# motor_controller.net
KiCad netlist of a schematic drawn in Altium Designer
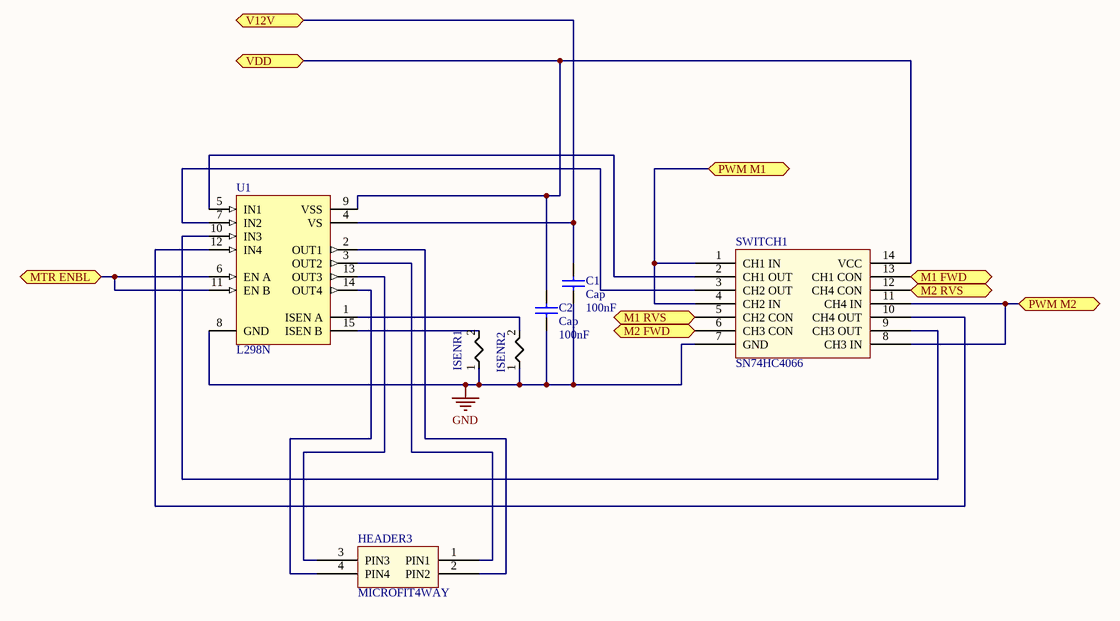
[diagram p0: motor_controller.SchDoc]

(export (version "E")
  (design (tool "Eeschema 10.0.6"))
  (components
    (comp (ref "C1")
      (value "Cap")
      (footprint "RAD-0.3")
      (description "Capacitor")
      (fields (field (name "ALTIUM_VALUE") "100nF") (field (name "PUBLISHER") "Altium Limited"))
      (libsource (lib "Miscellaneous Devices") (part "Cap"))
    )
    (comp (ref "C2")
      (value "Cap")
      (footprint "RAD-0.3")
      (description "Capacitor")
      (fields (field (name "ALTIUM_VALUE") "100nF") (field (name "PUBLISHER") "Altium Limited"))
      (libsource (lib "Miscellaneous Devices") (part "Cap"))
    )
    (comp (ref "HEADER3")
      (value "MICROFIT4WAY")
      (footprint "MULTIFIT-4WAY")
      (description "MICROFIT4WAY HEADER")
      (libsource (lib "MICROFIT_4WAY") (part "MICROFIT4WAY HEADER"))
    )
    (comp (ref "ISENR1")
      (value "CURRENT SENSE RESISTOR")
      (footprint "CURRENT_SENSE_RESISTOR")
      (libsource (lib "CURRENT_SENSE_R") (part "CURRENT SENSE RESISTOR"))
    )
    (comp (ref "ISENR2")
      (value "CURRENT SENSE RESISTOR")
      (footprint "CURRENT_SENSE_RESISTOR")
      (libsource (lib "CURRENT_SENSE_R") (part "CURRENT SENSE RESISTOR"))
    )
    (comp (ref "SWITCH1")
      (value "SN74HC4066")
      (footprint "SN74HC4066_DIP")
      (description "SN74HC4066 SWITCH")
      (libsource (lib "SN74HC4066") (part "SN74HC4066 SWITCH"))
    )
    (comp (ref "U1")
      (value "L298N")
      (footprint "Multiwatt15V")
      (description "Dual Full Bridge Driver")
      (fields (field (name "PUBLISHER") "Altium Limited"))
      (libsource (lib "ST Interface DC Motor Controller") (part "L298N"))
    )
  )
  (nets
    (net (code "1") (name "/M1 FWD") (class "Default")
      (node (ref "SWITCH1") (pin "13") (pinfunction "CH1_CON_13") (pintype "passive"))
    )
    (net (code "2") (name "/M1 RVS") (class "Default")
      (node (ref "SWITCH1") (pin "5") (pinfunction "CH2_CON_5") (pintype "passive"))
    )
    (net (code "3") (name "/M2 FWD") (class "Default")
      (node (ref "SWITCH1") (pin "6") (pinfunction "CH3_CON_6") (pintype "passive"))
    )
    (net (code "4") (name "/M2 RVS") (class "Default")
      (node (ref "SWITCH1") (pin "12") (pinfunction "CH4_CON_12") (pintype "passive"))
    )
    (net (code "5") (name "/MTR ENBL") (class "Default")
      (node (ref "U1") (pin "11") (pinfunction "EN_B_11") (pintype "input"))
      (node (ref "U1") (pin "6") (pinfunction "EN_A_6") (pintype "input"))
    )
    (net (code "6") (name "/PWM M1") (class "Default")
      (node (ref "SWITCH1") (pin "1") (pinfunction "CH1_IN_1") (pintype "passive"))
      (node (ref "SWITCH1") (pin "4") (pinfunction "CH2_IN_4") (pintype "passive"))
    )
    (net (code "7") (name "/PWM M2") (class "Default")
      (node (ref "SWITCH1") (pin "11") (pinfunction "CH4_IN_11") (pintype "passive"))
      (node (ref "SWITCH1") (pin "8") (pinfunction "CH3_IN_8") (pintype "passive"))
    )
    (net (code "8") (name "/V12V") (class "Default")
      (node (ref "C1") (pin "2") (pinfunction "2_2") (pintype "passive"))
      (node (ref "U1") (pin "4") (pinfunction "VS_4") (pintype "power_in"))
    )
    (net (code "9") (name "/VDD") (class "Default")
      (node (ref "C2") (pin "2") (pinfunction "2_2") (pintype "passive"))
      (node (ref "SWITCH1") (pin "14") (pinfunction "VCC_14") (pintype "passive"))
      (node (ref "U1") (pin "9") (pinfunction "VSS_9") (pintype "power_in"))
    )
    (net (code "10") (name "GND") (class "Default")
      (node (ref "C1") (pin "1") (pinfunction "1_1") (pintype "passive"))
      (node (ref "C2") (pin "1") (pinfunction "1_1") (pintype "passive"))
      (node (ref "ISENR1") (pin "1") (pinfunction "PIN1_1") (pintype "passive"))
      (node (ref "ISENR2") (pin "1") (pinfunction "PIN1_1") (pintype "passive"))
      (node (ref "SWITCH1") (pin "7") (pinfunction "GND_7") (pintype "passive"))
      (node (ref "U1") (pin "8") (pinfunction "GND_8") (pintype "power_in"))
    )
    (net (code "11") (name "Net-(HEADER3-PIN1)") (class "Default")
      (node (ref "HEADER3") (pin "1") (pinfunction "PIN1_1") (pintype "passive"))
      (node (ref "U1") (pin "3") (pinfunction "OUT2_3") (pintype "output"))
    )
    (net (code "12") (name "Net-(HEADER3-PIN2)") (class "Default")
      (node (ref "HEADER3") (pin "2") (pinfunction "PIN2_2") (pintype "passive"))
      (node (ref "U1") (pin "2") (pinfunction "OUT1_2") (pintype "output"))
    )
    (net (code "13") (name "Net-(HEADER3-PIN3)") (class "Default")
      (node (ref "HEADER3") (pin "3") (pinfunction "PIN3_3") (pintype "passive"))
      (node (ref "U1") (pin "13") (pinfunction "OUT3_13") (pintype "output"))
    )
    (net (code "14") (name "Net-(HEADER3-PIN4)") (class "Default")
      (node (ref "HEADER3") (pin "4") (pinfunction "PIN4_4") (pintype "passive"))
      (node (ref "U1") (pin "14") (pinfunction "OUT4_14") (pintype "output"))
    )
    (net (code "15") (name "Net-(ISENR1-PIN2)") (class "Default")
      (node (ref "ISENR1") (pin "2") (pinfunction "PIN2_2") (pintype "passive"))
      (node (ref "U1") (pin "15") (pinfunction "ISEN_B_15") (pintype "passive"))
    )
    (net (code "16") (name "Net-(ISENR2-PIN2)") (class "Default")
      (node (ref "ISENR2") (pin "2") (pinfunction "PIN2_2") (pintype "passive"))
      (node (ref "U1") (pin "1") (pinfunction "ISEN_A_1") (pintype "passive"))
    )
    (net (code "17") (name "Net-(SWITCH1-CH1_OUT)") (class "Default")
      (node (ref "SWITCH1") (pin "2") (pinfunction "CH1_OUT_2") (pintype "passive"))
      (node (ref "U1") (pin "5") (pinfunction "IN1_5") (pintype "input"))
    )
    (net (code "18") (name "Net-(SWITCH1-CH2_OUT)") (class "Default")
      (node (ref "SWITCH1") (pin "3") (pinfunction "CH2_OUT_3") (pintype "passive"))
      (node (ref "U1") (pin "7") (pinfunction "IN2_7") (pintype "input"))
    )
    (net (code "19") (name "Net-(SWITCH1-CH3_OUT)") (class "Default")
      (node (ref "SWITCH1") (pin "9") (pinfunction "CH3_OUT_9") (pintype "passive"))
      (node (ref "U1") (pin "10") (pinfunction "IN3_10") (pintype "input"))
    )
    (net (code "20") (name "Net-(SWITCH1-CH4_OUT)") (class "Default")
      (node (ref "SWITCH1") (pin "10") (pinfunction "CH4_OUT_10") (pintype "passive"))
      (node (ref "U1") (pin "12") (pinfunction "IN4_12") (pintype "input"))
    )
  )
)
